# TP4056.net
KiCad netlist of a schematic drawn in Altium Designer
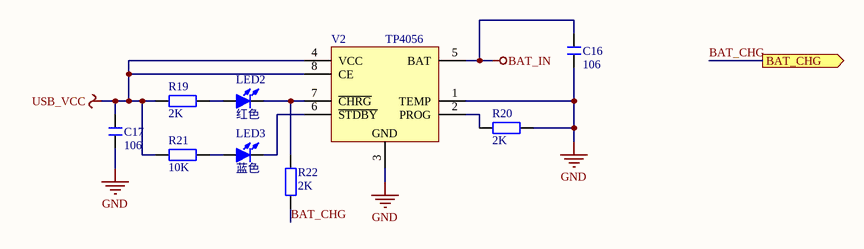
[diagram p0: TP4056电池管理模块.SchDoc]

(export (version "E")
  (design (tool "Eeschema 10.0.6"))
  (components
    (comp (ref "C16")
      (value "106")
      (footprint "C 0603_L")
      (description "无极性贴片电容")
      (fields (field (name "版权归属") "黎明电子style"))
      (libsource (lib "3.3   - 电容capacitor") (part "C"))
    )
    (comp (ref "C17")
      (value "106")
      (footprint "C 0603_L")
      (description "无极性贴片电容")
      (fields (field (name "版权归属") "黎明电子style"))
      (libsource (lib "3.3   - 电容capacitor") (part "C"))
    )
    (comp (ref "LED2")
      (value "红色")
      (footprint "LED 0603R")
      (description "贴片LED")
      (fields (field (name "版权归属") "源创客"))
      (libsource (lib "9.1   - LED") (part "LED-SMD"))
    )
    (comp (ref "LED3")
      (value "蓝色")
      (footprint "LED 0603B")
      (description "贴片LED")
      (fields (field (name "版权归属") "源创客"))
      (libsource (lib "9.1   - LED") (part "LED-SMD"))
    )
    (comp (ref "R19")
      (value "2K")
      (footprint "R 0603_L")
      (description "贴片电阻")
      (fields (field (name "版权归属") "黎明电子style"))
      (libsource (lib "3.4   - 电阻Resistor") (part "R"))
    )
    (comp (ref "R20")
      (value "2K")
      (footprint "R 0603_L")
      (description "贴片电阻")
      (fields (field (name "版权归属") "黎明电子style"))
      (libsource (lib "3.4   - 电阻Resistor") (part "R"))
    )
    (comp (ref "R21")
      (value "10K")
      (footprint "R 0603_L")
      (description "贴片电阻")
      (fields (field (name "版权归属") "黎明电子style"))
      (libsource (lib "3.4   - 电阻Resistor") (part "R"))
    )
    (comp (ref "R22")
      (value "2K")
      (footprint "R 0603_L")
      (description "贴片电阻")
      (fields (field (name "版权归属") "黎明电子style"))
      (libsource (lib "3.4   - 电阻Resistor") (part "R"))
    )
    (comp (ref "V2")
      (value "TP4056")
      (footprint "SOP8_L")
      (description "锂电池充电管理")
      (fields (field (name "版权归属") "源创客"))
      (libsource (lib "1.3   - 电源类芯片") (part "TP4056"))
    )
  )
  (nets
    (net (code "1") (name "/BAT_CHG") (class "Default")
      (node (ref "R22") (pin "2") (pinfunction "2_2") (pintype "passive"))
    )
    (net (code "2") (name "BAT_IN") (class "Default")
      (node (ref "C16") (pin "1") (pinfunction "1_1") (pintype "passive"))
      (node (ref "V2") (pin "5") (pinfunction "BAT_5") (pintype "passive"))
    )
    (net (code "3") (name "GND") (class "Default")
      (node (ref "C16") (pin "2") (pinfunction "2_2") (pintype "passive"))
      (node (ref "C17") (pin "1") (pinfunction "1_1") (pintype "passive"))
      (node (ref "R20") (pin "1") (pinfunction "1_1") (pintype "passive"))
      (node (ref "V2") (pin "1") (pinfunction "TEMP_1") (pintype "passive"))
      (node (ref "V2") (pin "3") (pinfunction "GND_3") (pintype "passive"))
    )
    (net (code "4") (name "Net-(LED2-A)") (class "Default")
      (node (ref "LED2") (pin "1") (pinfunction "A_1") (pintype "passive"))
      (node (ref "R19") (pin "1") (pinfunction "1_1") (pintype "passive"))
    )
    (net (code "5") (name "Net-(LED2-K)") (class "Default")
      (node (ref "LED2") (pin "2") (pinfunction "K_2") (pintype "passive"))
      (node (ref "R22") (pin "1") (pinfunction "1_1") (pintype "passive"))
      (node (ref "V2") (pin "7") (pinfunction "~{CHRG}_7") (pintype "passive"))
    )
    (net (code "6") (name "Net-(LED3-A)") (class "Default")
      (node (ref "LED3") (pin "1") (pinfunction "A_1") (pintype "passive"))
      (node (ref "R21") (pin "1") (pinfunction "1_1") (pintype "passive"))
    )
    (net (code "7") (name "Net-(LED3-K)") (class "Default")
      (node (ref "LED3") (pin "2") (pinfunction "K_2") (pintype "passive"))
      (node (ref "V2") (pin "6") (pinfunction "~{STDBY}_6") (pintype "passive"))
    )
    (net (code "8") (name "Net-(V2-PROG)") (class "Default")
      (node (ref "R20") (pin "2") (pinfunction "2_2") (pintype "passive"))
      (node (ref "V2") (pin "2") (pinfunction "PROG_2") (pintype "passive"))
    )
    (net (code "9") (name "USB_VCC") (class "Default")
      (node (ref "C17") (pin "2") (pinfunction "2_2") (pintype "passive"))
      (node (ref "R19") (pin "2") (pinfunction "2_2") (pintype "passive"))
      (node (ref "R21") (pin "2") (pinfunction "2_2") (pintype "passive"))
      (node (ref "V2") (pin "4") (pinfunction "VCC_4") (pintype "passive"))
      (node (ref "V2") (pin "8") (pinfunction "CE_8") (pintype "passive"))
    )
  )
)
